# F446RET6.net
KiCad netlist of a schematic drawn in EAGLE
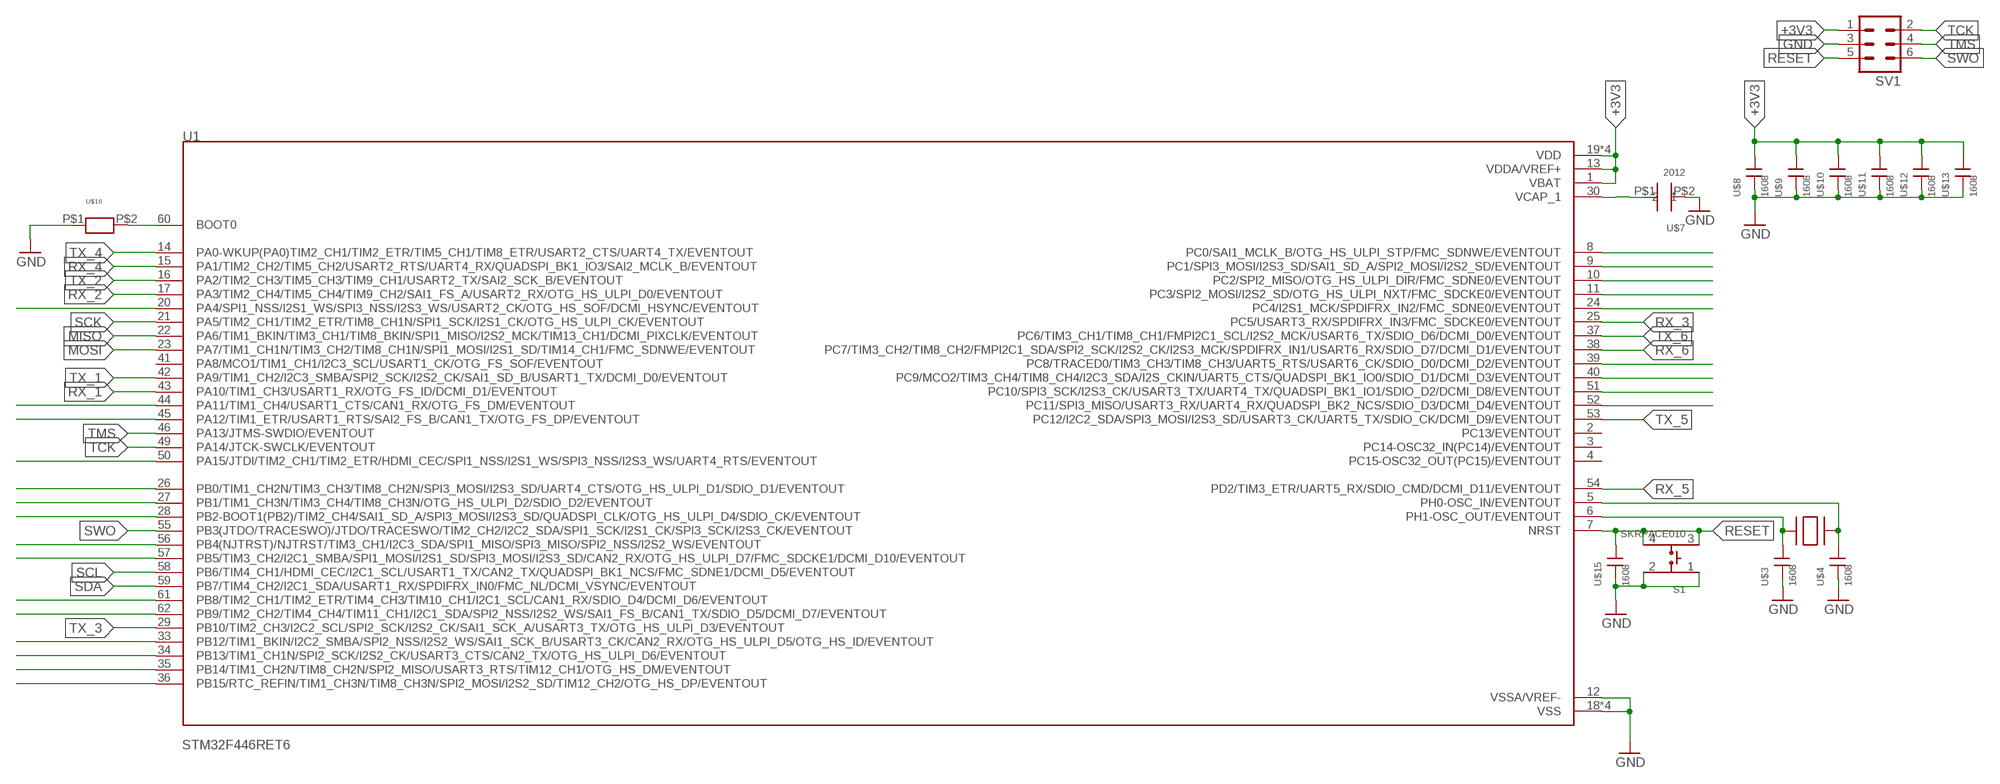
[diagram p0: schematic, sheet 1]

(export (version "E")
  (design (tool "Eeschema 10.0.6"))
  (components
    (comp (ref "S1")
      (value "SKRPACE010")
      (footprint "eagle-import:SW_SKRPACE010")
      (fields (field (name "MF") "ALPS"))
      (libsource (lib "eagle-import") (part "SKRPACE010"))
    )
    (comp (ref "SV1")
      (value "ML6")
      (footprint "eagle-import:ML6")
      (libsource (lib "eagle-import") (part "ML6"))
    )
    (comp (ref "U$1")
      (value "SUISYOU")
      (footprint "eagle-import:水晶")
      (libsource (lib "eagle-import") (part "SUISYOU"))
    )
    (comp (ref "U$3")
      (value "1608")
      (footprint "eagle-import:CON")
      (libsource (lib "eagle-import") (part "1608"))
    )
    (comp (ref "U$4")
      (value "1608")
      (footprint "eagle-import:CON")
      (libsource (lib "eagle-import") (part "1608"))
    )
    (comp (ref "U$7")
      (value "2012")
      (footprint "eagle-import:2012")
      (libsource (lib "eagle-import") (part "2012"))
    )
    (comp (ref "U$8")
      (value "1608")
      (footprint "eagle-import:CON")
      (libsource (lib "eagle-import") (part "1608"))
    )
    (comp (ref "U$9")
      (value "1608")
      (footprint "eagle-import:CON")
      (libsource (lib "eagle-import") (part "1608"))
    )
    (comp (ref "U$10")
      (value "1608")
      (footprint "eagle-import:CON")
      (libsource (lib "eagle-import") (part "1608"))
    )
    (comp (ref "U$11")
      (value "1608")
      (footprint "eagle-import:CON")
      (libsource (lib "eagle-import") (part "1608"))
    )
    (comp (ref "U$12")
      (value "1608")
      (footprint "eagle-import:CON")
      (libsource (lib "eagle-import") (part "1608"))
    )
    (comp (ref "U$13")
      (value "1608")
      (footprint "eagle-import:CON")
      (libsource (lib "eagle-import") (part "1608"))
    )
    (comp (ref "U$15")
      (value "1608")
      (footprint "eagle-import:CON")
      (libsource (lib "eagle-import") (part "1608"))
    )
    (comp (ref "U$16")
      (value "R")
      (footprint "eagle-import:1608")
      (libsource (lib "eagle-import") (part "R"))
    )
    (comp (ref "U1")
      (value "STM32F446RET6")
      (footprint "eagle-import:QFP50P1200X1200X160-64N")
      (fields (field (name "MF") "STMicroelectronics"))
      (libsource (lib "eagle-import") (part "STM32F446RET6"))
    )
  )
  (nets
    (net (code "1") (name "+3V3") (class "Default")
      (node (ref "SV1") (pin "1") (pinfunction "1_1") (pintype "passive"))
      (node (ref "U$10") (pin "P$1") (pinfunction "1_P$1") (pintype "bidirectional"))
      (node (ref "U$11") (pin "P$1") (pinfunction "1_P$1") (pintype "bidirectional"))
      (node (ref "U$12") (pin "P$1") (pinfunction "1_P$1") (pintype "bidirectional"))
      (node (ref "U$13") (pin "P$1") (pinfunction "1_P$1") (pintype "bidirectional"))
      (node (ref "U$8") (pin "P$1") (pinfunction "1_P$1") (pintype "bidirectional"))
      (node (ref "U$9") (pin "P$1") (pinfunction "1_P$1") (pintype "bidirectional"))
      (node (ref "U1") (pin "1") (pinfunction "VBAT_1") (pintype "power_in"))
      (node (ref "U1") (pin "13") (pinfunction "VDDA/VREF+_13") (pintype "power_in"))
      (node (ref "U1") (pin "19") (pinfunction "VDD_19") (pintype "power_in"))
      (node (ref "U1") (pin "32") (pinfunction "VDD_32") (pintype "power_in"))
      (node (ref "U1") (pin "48") (pinfunction "VDD_48") (pintype "power_in"))
      (node (ref "U1") (pin "64") (pinfunction "VDD_64") (pintype "power_in"))
    )
    (net (code "2") (name "GND") (class "Default")
      (node (ref "S1") (pin "1") (pinfunction "1_1") (pintype "bidirectional"))
      (node (ref "S1") (pin "2") (pinfunction "2_2") (pintype "bidirectional"))
      (node (ref "SV1") (pin "3") (pinfunction "3_3") (pintype "passive"))
      (node (ref "U$10") (pin "P$2") (pinfunction "2_P$2") (pintype "bidirectional"))
      (node (ref "U$11") (pin "P$2") (pinfunction "2_P$2") (pintype "bidirectional"))
      (node (ref "U$12") (pin "P$2") (pinfunction "2_P$2") (pintype "bidirectional"))
      (node (ref "U$13") (pin "P$2") (pinfunction "2_P$2") (pintype "bidirectional"))
      (node (ref "U$15") (pin "P$2") (pinfunction "2_P$2") (pintype "bidirectional"))
      (node (ref "U$16") (pin "P$1") (pinfunction "P$1_P$1") (pintype "bidirectional"))
      (node (ref "U$3") (pin "P$2") (pinfunction "2_P$2") (pintype "bidirectional"))
      (node (ref "U$4") (pin "P$2") (pinfunction "2_P$2") (pintype "bidirectional"))
      (node (ref "U$7") (pin "P$2") (pinfunction "2_P$2") (pintype "bidirectional"))
      (node (ref "U$8") (pin "P$2") (pinfunction "2_P$2") (pintype "bidirectional"))
      (node (ref "U$9") (pin "P$2") (pinfunction "2_P$2") (pintype "bidirectional"))
      (node (ref "U1") (pin "12") (pinfunction "VSSA/VREF-_12") (pintype "power_in"))
      (node (ref "U1") (pin "18") (pinfunction "VSS_18") (pintype "power_in"))
      (node (ref "U1") (pin "31") (pinfunction "VSS_31") (pintype "power_in"))
      (node (ref "U1") (pin "47") (pinfunction "VSS_47") (pintype "power_in"))
      (node (ref "U1") (pin "63") (pinfunction "VSS_63") (pintype "power_in"))
    )
    (net (code "3") (name "MISO") (class "Default")
      (node (ref "U1") (pin "22") (pinfunction "PA6/TIM1_BKIN/TIM3_CH1/TIM8_BKIN/SPI1_MISO/I2S2_MCK/TIM13_CH1/DCMI_PIXCLK/EVENTOUT_22") (pintype "bidirectional"))
    )
    (net (code "4") (name "MOSI") (class "Default")
      (node (ref "U1") (pin "23") (pinfunction "PA7/TIM1_CH1N/TIM3_CH2/TIM8_CH1N/SPI1_MOSI/I2S1_SD/TIM14_CH1/FMC_SDNWE/EVENTOUT_23") (pintype "bidirectional"))
    )
    (net (code "5") (name "Net-(U$3-1)") (class "Default")
      (node (ref "U$1") (pin "P$1") (pinfunction "P$1_P$1") (pintype "bidirectional"))
      (node (ref "U$3") (pin "P$1") (pinfunction "1_P$1") (pintype "bidirectional"))
      (node (ref "U1") (pin "6") (pinfunction "PH1-OSC_OUT/EVENTOUT_6") (pintype "bidirectional"))
    )
    (net (code "6") (name "Net-(U$4-1)") (class "Default")
      (node (ref "U$1") (pin "P$2") (pinfunction "P$2_P$2") (pintype "bidirectional"))
      (node (ref "U$4") (pin "P$1") (pinfunction "1_P$1") (pintype "bidirectional"))
      (node (ref "U1") (pin "5") (pinfunction "PH0-OSC_IN/EVENTOUT_5") (pintype "bidirectional"))
    )
    (net (code "7") (name "Net-(U$7-1)") (class "Default")
      (node (ref "U$7") (pin "P$1") (pinfunction "1_P$1") (pintype "bidirectional"))
      (node (ref "U1") (pin "30") (pinfunction "VCAP_1_30") (pintype "power_in"))
    )
    (net (code "8") (name "Net-(U1-BOOT0)") (class "Default")
      (node (ref "U$16") (pin "P$2") (pinfunction "P$2_P$2") (pintype "bidirectional"))
      (node (ref "U1") (pin "60") (pinfunction "BOOT0_60") (pintype "input"))
    )
    (net (code "9") (name "RESET") (class "Default")
      (node (ref "S1") (pin "3") (pinfunction "3_3") (pintype "bidirectional"))
      (node (ref "S1") (pin "4") (pinfunction "4_4") (pintype "bidirectional"))
      (node (ref "SV1") (pin "5") (pinfunction "5_5") (pintype "passive"))
      (node (ref "U$15") (pin "P$1") (pinfunction "1_P$1") (pintype "bidirectional"))
      (node (ref "U1") (pin "7") (pinfunction "NRST_7") (pintype "bidirectional"))
    )
    (net (code "10") (name "RX_1") (class "Default")
      (node (ref "U1") (pin "43") (pinfunction "PA10/TIM1_CH3/USART1_RX/OTG_FS_ID/DCMI_D1/EVENTOUT_43") (pintype "bidirectional"))
    )
    (net (code "11") (name "RX_2") (class "Default")
      (node (ref "U1") (pin "17") (pinfunction "PA3/TIM2_CH4/TIM5_CH4/TIM9_CH2/SAI1_FS_A/USART2_RX/OTG_HS_ULPI_D0/EVENTOUT_17") (pintype "bidirectional"))
    )
    (net (code "12") (name "RX_3") (class "Default")
      (node (ref "U1") (pin "25") (pinfunction "PC5/USART3_RX/SPDIFRX_IN3/FMC_SDCKE0/EVENTOUT_25") (pintype "bidirectional"))
    )
    (net (code "13") (name "RX_4") (class "Default")
      (node (ref "U1") (pin "15") (pinfunction "PA1/TIM2_CH2/TIM5_CH2/USART2_RTS/UART4_RX/QUADSPI_BK1_IO3/SAI2_MCLK_B/EVENTOUT_15") (pintype "bidirectional"))
    )
    (net (code "14") (name "RX_5") (class "Default")
      (node (ref "U1") (pin "54") (pinfunction "PD2/TIM3_ETR/UART5_RX/SDIO_CMD/DCMI_D11/EVENTOUT_54") (pintype "bidirectional"))
    )
    (net (code "15") (name "RX_6") (class "Default")
      (node (ref "U1") (pin "38") (pinfunction "PC7/TIM3_CH2/TIM8_CH2/FMPI2C1_SDA/SPI2_SCK/I2S2_CK/I2S3_MCK/SPDIFRX_IN1/USART6_RX/SDIO_D7/DCMI_D1/EVENTOUT_38") (pintype "bidirectional"))
    )
    (net (code "16") (name "SCK") (class "Default")
      (node (ref "U1") (pin "21") (pinfunction "PA5/TIM2_CH1/TIM2_ETR/TIM8_CH1N/SPI1_SCK/I2S1_CK/OTG_HS_ULPI_CK/EVENTOUT_21") (pintype "bidirectional"))
    )
    (net (code "17") (name "SCL") (class "Default")
      (node (ref "U1") (pin "58") (pinfunction "PB6/TIM4_CH1/HDMI_CEC/I2C1_SCL/USART1_TX/CAN2_TX/QUADSPI_BK1_NCS/FMC_SDNE1/DCMI_D5/EVENTOUT_58") (pintype "bidirectional"))
    )
    (net (code "18") (name "SDA") (class "Default")
      (node (ref "U1") (pin "59") (pinfunction "PB7/TIM4_CH2/I2C1_SDA/USART1_RX/SPDIFRX_IN0/FMC_NL/DCMI_VSYNC/EVENTOUT_59") (pintype "bidirectional"))
    )
    (net (code "19") (name "SWO") (class "Default")
      (node (ref "SV1") (pin "6") (pinfunction "6_6") (pintype "passive"))
      (node (ref "U1") (pin "55") (pinfunction "PB3(JTDO/TRACESWO)/JTDO/TRACESWO/TIM2_CH2/I2C2_SDA/SPI1_SCK/I2S1_CK/SPI3_SCK/I2S3_CK/EVENTOUT_55") (pintype "bidirectional"))
    )
    (net (code "20") (name "TCK") (class "Default")
      (node (ref "SV1") (pin "2") (pinfunction "2_2") (pintype "passive"))
      (node (ref "U1") (pin "49") (pinfunction "PA14/JTCK-SWCLK/EVENTOUT_49") (pintype "bidirectional"))
    )
    (net (code "21") (name "TMS") (class "Default")
      (node (ref "SV1") (pin "4") (pinfunction "4_4") (pintype "passive"))
      (node (ref "U1") (pin "46") (pinfunction "PA13/JTMS-SWDIO/EVENTOUT_46") (pintype "bidirectional"))
    )
    (net (code "22") (name "TX_1") (class "Default")
      (node (ref "U1") (pin "42") (pinfunction "PA9/TIM1_CH2/I2C3_SMBA/SPI2_SCK/I2S2_CK/SAI1_SD_B/USART1_TX/DCMI_D0/EVENTOUT_42") (pintype "bidirectional"))
    )
    (net (code "23") (name "TX_2") (class "Default")
      (node (ref "U1") (pin "16") (pinfunction "PA2/TIM2_CH3/TIM5_CH3/TIM9_CH1/USART2_TX/SAI2_SCK_B/EVENTOUT_16") (pintype "bidirectional"))
    )
    (net (code "24") (name "TX_3") (class "Default")
      (node (ref "U1") (pin "29") (pinfunction "PB10/TIM2_CH3/I2C2_SCL/SPI2_SCK/I2S2_CK/SAI1_SCK_A/USART3_TX/OTG_HS_ULPI_D3/EVENTOUT_29") (pintype "bidirectional"))
    )
    (net (code "25") (name "TX_4") (class "Default")
      (node (ref "U1") (pin "14") (pinfunction "PA0-WKUP(PA0)TIM2_CH1/TIM2_ETR/TIM5_CH1/TIM8_ETR/USART2_CTS/UART4_TX/EVENTOUT_14") (pintype "bidirectional"))
    )
    (net (code "26") (name "TX_5") (class "Default")
      (node (ref "U1") (pin "53") (pinfunction "PC12/I2C2_SDA/SPI3_MOSI/I2S3_SD/USART3_CK/UART5_TX/SDIO_CK/DCMI_D9/EVENTOUT_53") (pintype "bidirectional"))
    )
    (net (code "27") (name "TX_6") (class "Default")
      (node (ref "U1") (pin "37") (pinfunction "PC6/TIM3_CH1/TIM8_CH1/FMPI2C1_SCL/I2S2_MCK/USART6_TX/SDIO_D6/DCMI_D0/EVENTOUT_37") (pintype "bidirectional"))
    )
    (net (code "28") (name "unconnected-(U1-PA4{slash}SPI1_NSS{slash}I2S1_WS{slash}SPI3_NSS{slash}I2S3_WS{slash}USART2_CK{slash}OTG_HS_SOF{slash}DCMI_HSYNC{slash}EVENTOUT-Pad20)") (class "Default")
      (node (ref "U1") (pin "20") (pinfunction "PA4/SPI1_NSS/I2S1_WS/SPI3_NSS/I2S3_WS/USART2_CK/OTG_HS_SOF/DCMI_HSYNC/EVENTOUT_20") (pintype "bidirectional"))
    )
    (net (code "29") (name "unconnected-(U1-PA8{slash}MCO1{slash}TIM1_CH1{slash}I2C3_SCL{slash}USART1_CK{slash}OTG_FS_SOF{slash}EVENTOUT-Pad41)") (class "Default")
      (node (ref "U1") (pin "41") (pinfunction "PA8/MCO1/TIM1_CH1/I2C3_SCL/USART1_CK/OTG_FS_SOF/EVENTOUT_41") (pintype "bidirectional"))
    )
    (net (code "30") (name "unconnected-(U1-PA11{slash}TIM1_CH4{slash}USART1_CTS{slash}CAN1_RX{slash}OTG_FS_DM{slash}EVENTOUT-Pad44)") (class "Default")
      (node (ref "U1") (pin "44") (pinfunction "PA11/TIM1_CH4/USART1_CTS/CAN1_RX/OTG_FS_DM/EVENTOUT_44") (pintype "bidirectional"))
    )
    (net (code "31") (name "unconnected-(U1-PA12{slash}TIM1_ETR{slash}USART1_RTS{slash}SAI2_FS_B{slash}CAN1_TX{slash}OTG_FS_DP{slash}EVENTOUT-Pad45)") (class "Default")
      (node (ref "U1") (pin "45") (pinfunction "PA12/TIM1_ETR/USART1_RTS/SAI2_FS_B/CAN1_TX/OTG_FS_DP/EVENTOUT_45") (pintype "bidirectional"))
    )
    (net (code "32") (name "unconnected-(U1-PA15{slash}JTDI{slash}TIM2_CH1{slash}TIM2_ETR{slash}HDMI_CEC{slash}SPI1_NSS{slash}I2S1_WS{slash}SPI3_NSS{slash}I2S3_WS{slash}UART4_RTS{slash}EVENTOUT-Pad50)") (class "Default")
      (node (ref "U1") (pin "50") (pinfunction "PA15/JTDI/TIM2_CH1/TIM2_ETR/HDMI_CEC/SPI1_NSS/I2S1_WS/SPI3_NSS/I2S3_WS/UART4_RTS/EVENTOUT_50") (pintype "bidirectional"))
    )
    (net (code "33") (name "unconnected-(U1-PB0{slash}TIM1_CH2N{slash}TIM3_CH3{slash}TIM8_CH2N{slash}SPI3_MOSI{slash}I2S3_SD{slash}UART4_CTS{slash}OTG_HS_ULPI_D1{slash}SDIO_D1{slash}EVENTOUT-Pad26)") (class "Default")
      (node (ref "U1") (pin "26") (pinfunction "PB0/TIM1_CH2N/TIM3_CH3/TIM8_CH2N/SPI3_MOSI/I2S3_SD/UART4_CTS/OTG_HS_ULPI_D1/SDIO_D1/EVENTOUT_26") (pintype "bidirectional"))
    )
    (net (code "34") (name "unconnected-(U1-PB1{slash}TIM1_CH3N{slash}TIM3_CH4{slash}TIM8_CH3N{slash}OTG_HS_ULPI_D2{slash}SDIO_D2{slash}EVENTOUT-Pad27)") (class "Default")
      (node (ref "U1") (pin "27") (pinfunction "PB1/TIM1_CH3N/TIM3_CH4/TIM8_CH3N/OTG_HS_ULPI_D2/SDIO_D2/EVENTOUT_27") (pintype "bidirectional"))
    )
    (net (code "35") (name "unconnected-(U1-PB2-BOOT1(PB2){slash}TIM2_CH4{slash}SAI1_SD_A{slash}SPI3_MOSI{slash}I2S3_SD{slash}QUADSPI_CLK{slash}OTG_HS_ULPI_D4{slash}SDIO_CK{slash}EVENTOUT-Pad28)") (class "Default")
      (node (ref "U1") (pin "28") (pinfunction "PB2-BOOT1(PB2)/TIM2_CH4/SAI1_SD_A/SPI3_MOSI/I2S3_SD/QUADSPI_CLK/OTG_HS_ULPI_D4/SDIO_CK/EVENTOUT_28") (pintype "bidirectional"))
    )
    (net (code "36") (name "unconnected-(U1-PB4(NJTRST){slash}NJTRST{slash}TIM3_CH1{slash}I2C3_SDA{slash}SPI1_MISO{slash}SPI3_MISO{slash}SPI2_NSS{slash}I2S2_WS{slash}EVENTOUT-Pad56)") (class "Default")
      (node (ref "U1") (pin "56") (pinfunction "PB4(NJTRST)/NJTRST/TIM3_CH1/I2C3_SDA/SPI1_MISO/SPI3_MISO/SPI2_NSS/I2S2_WS/EVENTOUT_56") (pintype "bidirectional"))
    )
    (net (code "37") (name "unconnected-(U1-PB5{slash}TIM3_CH2{slash}I2C1_SMBA{slash}SPI1_MOSI{slash}I2S1_SD{slash}SPI3_MOSI{slash}I2S3_SD{slash}CAN2_RX{slash}OTG_HS_ULPI_D7{slash}FMC_SDCKE1{slash}DCMI_D10{slash}EVENTOUT-Pad57)") (class "Default")
      (node (ref "U1") (pin "57") (pinfunction "PB5/TIM3_CH2/I2C1_SMBA/SPI1_MOSI/I2S1_SD/SPI3_MOSI/I2S3_SD/CAN2_RX/OTG_HS_ULPI_D7/FMC_SDCKE1/DCMI_D10/EVENTOUT_57") (pintype "bidirectional"))
    )
    (net (code "38") (name "unconnected-(U1-PB8{slash}TIM2_CH1{slash}TIM2_ETR{slash}TIM4_CH3{slash}TIM10_CH1{slash}I2C1_SCL{slash}CAN1_RX{slash}SDIO_D4{slash}DCMI_D6{slash}EVENTOUT-Pad61)") (class "Default")
      (node (ref "U1") (pin "61") (pinfunction "PB8/TIM2_CH1/TIM2_ETR/TIM4_CH3/TIM10_CH1/I2C1_SCL/CAN1_RX/SDIO_D4/DCMI_D6/EVENTOUT_61") (pintype "bidirectional"))
    )
    (net (code "39") (name "unconnected-(U1-PB9{slash}TIM2_CH2{slash}TIM4_CH4{slash}TIM11_CH1{slash}I2C1_SDA{slash}SPI2_NSS{slash}I2S2_WS{slash}SAI1_FS_B{slash}CAN1_TX{slash}SDIO_D5{slash}DCMI_D7{slash}EVENTOUT-Pad62)") (class "Default")
      (node (ref "U1") (pin "62") (pinfunction "PB9/TIM2_CH2/TIM4_CH4/TIM11_CH1/I2C1_SDA/SPI2_NSS/I2S2_WS/SAI1_FS_B/CAN1_TX/SDIO_D5/DCMI_D7/EVENTOUT_62") (pintype "bidirectional"))
    )
    (net (code "40") (name "unconnected-(U1-PB12{slash}TIM1_BKIN{slash}I2C2_SMBA{slash}SPI2_NSS{slash}I2S2_WS{slash}SAI1_SCK_B{slash}USART3_CK{slash}CAN2_RX{slash}OTG_HS_ULPI_D5{slash}OTG_HS_ID{slash}EVENTOUT-Pad33)") (class "Default")
      (node (ref "U1") (pin "33") (pinfunction "PB12/TIM1_BKIN/I2C2_SMBA/SPI2_NSS/I2S2_WS/SAI1_SCK_B/USART3_CK/CAN2_RX/OTG_HS_ULPI_D5/OTG_HS_ID/EVENTOUT_33") (pintype "bidirectional"))
    )
    (net (code "41") (name "unconnected-(U1-PB13{slash}TIM1_CH1N{slash}SPI2_SCK{slash}I2S2_CK{slash}USART3_CTS{slash}CAN2_TX{slash}OTG_HS_ULPI_D6{slash}EVENTOUT-Pad34)") (class "Default")
      (node (ref "U1") (pin "34") (pinfunction "PB13/TIM1_CH1N/SPI2_SCK/I2S2_CK/USART3_CTS/CAN2_TX/OTG_HS_ULPI_D6/EVENTOUT_34") (pintype "bidirectional"))
    )
    (net (code "42") (name "unconnected-(U1-PB14{slash}TIM1_CH2N{slash}TIM8_CH2N{slash}SPI2_MISO{slash}USART3_RTS{slash}TIM12_CH1{slash}OTG_HS_DM{slash}EVENTOUT-Pad35)") (class "Default")
      (node (ref "U1") (pin "35") (pinfunction "PB14/TIM1_CH2N/TIM8_CH2N/SPI2_MISO/USART3_RTS/TIM12_CH1/OTG_HS_DM/EVENTOUT_35") (pintype "bidirectional"))
    )
    (net (code "43") (name "unconnected-(U1-PB15{slash}RTC_REFIN{slash}TIM1_CH3N{slash}TIM8_CH3N{slash}SPI2_MOSI{slash}I2S2_SD{slash}TIM12_CH2{slash}OTG_HS_DP{slash}EVENTOUT-Pad36)") (class "Default")
      (node (ref "U1") (pin "36") (pinfunction "PB15/RTC_REFIN/TIM1_CH3N/TIM8_CH3N/SPI2_MOSI/I2S2_SD/TIM12_CH2/OTG_HS_DP/EVENTOUT_36") (pintype "bidirectional"))
    )
    (net (code "44") (name "unconnected-(U1-PC0{slash}SAI1_MCLK_B{slash}OTG_HS_ULPI_STP{slash}FMC_SDNWE{slash}EVENTOUT-Pad8)") (class "Default")
      (node (ref "U1") (pin "8") (pinfunction "PC0/SAI1_MCLK_B/OTG_HS_ULPI_STP/FMC_SDNWE/EVENTOUT_8") (pintype "bidirectional"))
    )
    (net (code "45") (name "unconnected-(U1-PC1{slash}SPI3_MOSI{slash}I2S3_SD{slash}SAI1_SD_A{slash}SPI2_MOSI{slash}I2S2_SD{slash}EVENTOUT-Pad9)") (class "Default")
      (node (ref "U1") (pin "9") (pinfunction "PC1/SPI3_MOSI/I2S3_SD/SAI1_SD_A/SPI2_MOSI/I2S2_SD/EVENTOUT_9") (pintype "bidirectional"))
    )
    (net (code "46") (name "unconnected-(U1-PC2{slash}SPI2_MISO{slash}OTG_HS_ULPI_DIR{slash}FMC_SDNE0{slash}EVENTOUT-Pad10)") (class "Default")
      (node (ref "U1") (pin "10") (pinfunction "PC2/SPI2_MISO/OTG_HS_ULPI_DIR/FMC_SDNE0/EVENTOUT_10") (pintype "bidirectional"))
    )
    (net (code "47") (name "unconnected-(U1-PC3{slash}SPI2_MOSI{slash}I2S2_SD{slash}OTG_HS_ULPI_NXT{slash}FMC_SDCKE0{slash}EVENTOUT-Pad11)") (class "Default")
      (node (ref "U1") (pin "11") (pinfunction "PC3/SPI2_MOSI/I2S2_SD/OTG_HS_ULPI_NXT/FMC_SDCKE0/EVENTOUT_11") (pintype "bidirectional"))
    )
    (net (code "48") (name "unconnected-(U1-PC4{slash}I2S1_MCK{slash}SPDIFRX_IN2{slash}FMC_SDNE0{slash}EVENTOUT-Pad24)") (class "Default")
      (node (ref "U1") (pin "24") (pinfunction "PC4/I2S1_MCK/SPDIFRX_IN2/FMC_SDNE0/EVENTOUT_24") (pintype "bidirectional"))
    )
    (net (code "49") (name "unconnected-(U1-PC8{slash}TRACED0{slash}TIM3_CH3{slash}TIM8_CH3{slash}UART5_RTS{slash}USART6_CK{slash}SDIO_D0{slash}DCMI_D2{slash}EVENTOUT-Pad39)") (class "Default")
      (node (ref "U1") (pin "39") (pinfunction "PC8/TRACED0/TIM3_CH3/TIM8_CH3/UART5_RTS/USART6_CK/SDIO_D0/DCMI_D2/EVENTOUT_39") (pintype "bidirectional"))
    )
    (net (code "50") (name "unconnected-(U1-PC9{slash}MCO2{slash}TIM3_CH4{slash}TIM8_CH4{slash}I2C3_SDA{slash}I2S_CKIN{slash}UART5_CTS{slash}QUADSPI_BK1_IO0{slash}SDIO_D1{slash}DCMI_D3{slash}EVENTOUT-Pad40)") (class "Default")
      (node (ref "U1") (pin "40") (pinfunction "PC9/MCO2/TIM3_CH4/TIM8_CH4/I2C3_SDA/I2S_CKIN/UART5_CTS/QUADSPI_BK1_IO0/SDIO_D1/DCMI_D3/EVENTOUT_40") (pintype "bidirectional"))
    )
    (net (code "51") (name "unconnected-(U1-PC10{slash}SPI3_SCK{slash}I2S3_CK{slash}USART3_TX{slash}UART4_TX{slash}QUADSPI_BK1_IO1{slash}SDIO_D2{slash}DCMI_D8{slash}EVENTOUT-Pad51)") (class "Default")
      (node (ref "U1") (pin "51") (pinfunction "PC10/SPI3_SCK/I2S3_CK/USART3_TX/UART4_TX/QUADSPI_BK1_IO1/SDIO_D2/DCMI_D8/EVENTOUT_51") (pintype "bidirectional"))
    )
    (net (code "52") (name "unconnected-(U1-PC11{slash}SPI3_MISO{slash}USART3_RX{slash}UART4_RX{slash}QUADSPI_BK2_NCS{slash}SDIO_D3{slash}DCMI_D4{slash}EVENTOUT-Pad52)") (class "Default")
      (node (ref "U1") (pin "52") (pinfunction "PC11/SPI3_MISO/USART3_RX/UART4_RX/QUADSPI_BK2_NCS/SDIO_D3/DCMI_D4/EVENTOUT_52") (pintype "bidirectional"))
    )
    (net (code "53") (name "unconnected-(U1-PC13{slash}EVENTOUT-Pad2)") (class "Default")
      (node (ref "U1") (pin "2") (pinfunction "PC13/EVENTOUT_2") (pintype "bidirectional"))
    )
    (net (code "54") (name "unconnected-(U1-PC14-OSC32_IN(PC14){slash}EVENTOUT-Pad3)") (class "Default")
      (node (ref "U1") (pin "3") (pinfunction "PC14-OSC32_IN(PC14)/EVENTOUT_3") (pintype "bidirectional"))
    )
    (net (code "55") (name "unconnected-(U1-PC15-OSC32_OUT(PC15){slash}EVENTOUT-Pad4)") (class "Default")
      (node (ref "U1") (pin "4") (pinfunction "PC15-OSC32_OUT(PC15)/EVENTOUT_4") (pintype "bidirectional"))
    )
  )
)
